# source.net
KiCad netlist of a schematic drawn in EasyEDA Pro
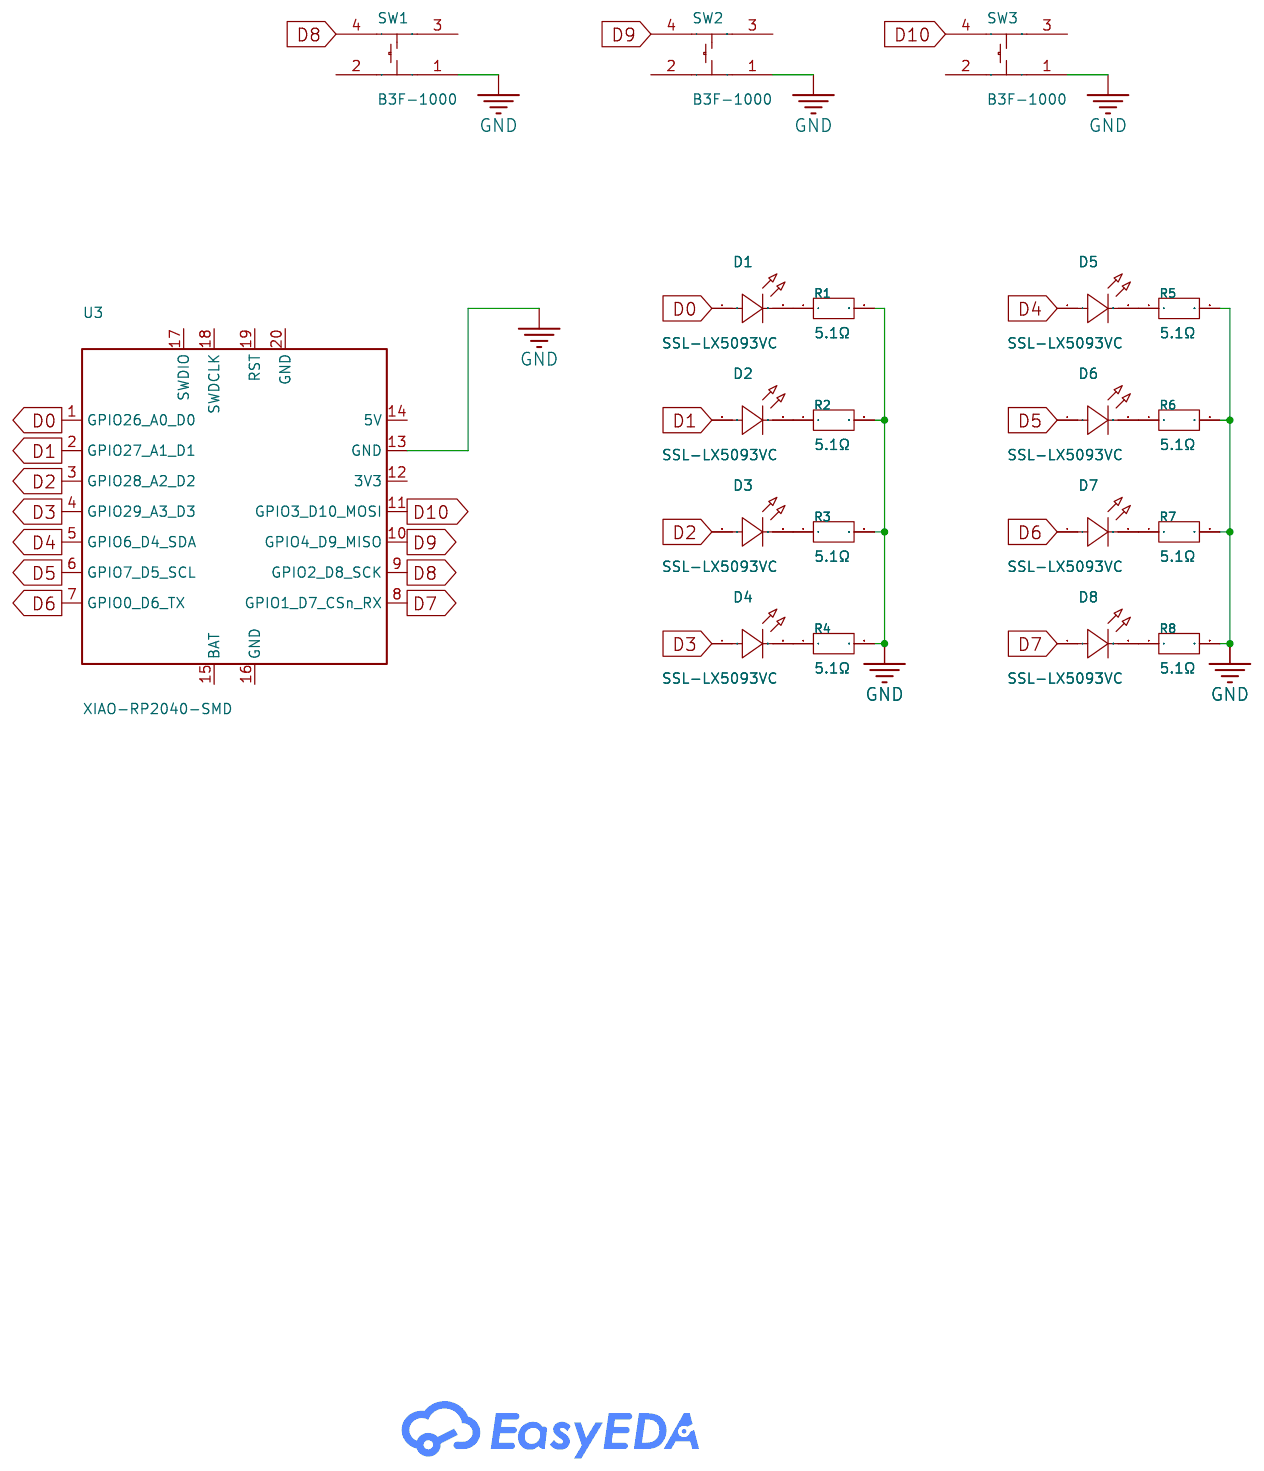
[diagram p0: schematic sheet]

(export (version "E")
  (design (tool "Eeschema 10.0.6"))
  (components
    (comp (ref "D1")
      (value "SSL-LX5093VC")
      (footprint "easyedapro:LED-TH_BD5.0-P2.54-FD")
      (fields (field (name "Manufacturer") "Kingbright"))
      (libsource (lib "easyedapro") (part "WP7113SGC"))
    )
    (comp (ref "D2")
      (value "SSL-LX5093VC")
      (footprint "easyedapro:LED-TH_BD5.0-P2.54-FD")
      (fields (field (name "Manufacturer") "Kingbright"))
      (libsource (lib "easyedapro") (part "WP7113SGC"))
    )
    (comp (ref "D3")
      (value "SSL-LX5093VC")
      (footprint "easyedapro:LED-TH_BD5.0-P2.54-FD")
      (fields (field (name "Manufacturer") "Kingbright"))
      (libsource (lib "easyedapro") (part "WP7113SGC"))
    )
    (comp (ref "D4")
      (value "SSL-LX5093VC")
      (footprint "easyedapro:LED-TH_BD5.0-P2.54-FD")
      (fields (field (name "Manufacturer") "Kingbright"))
      (libsource (lib "easyedapro") (part "WP7113SGC"))
    )
    (comp (ref "D5")
      (value "SSL-LX5093VC")
      (footprint "easyedapro:LED-TH_BD5.0-P2.54-FD")
      (fields (field (name "Manufacturer") "Kingbright"))
      (libsource (lib "easyedapro") (part "WP7113SGC"))
    )
    (comp (ref "D6")
      (value "SSL-LX5093VC")
      (footprint "easyedapro:LED-TH_BD5.0-P2.54-FD")
      (fields (field (name "Manufacturer") "Kingbright"))
      (libsource (lib "easyedapro") (part "WP7113SGC"))
    )
    (comp (ref "D7")
      (value "SSL-LX5093VC")
      (footprint "easyedapro:LED-TH_BD5.0-P2.54-FD")
      (fields (field (name "Manufacturer") "Kingbright"))
      (libsource (lib "easyedapro") (part "WP7113SGC"))
    )
    (comp (ref "D8")
      (value "SSL-LX5093VC")
      (footprint "easyedapro:LED-TH_BD5.0-P2.54-FD")
      (fields (field (name "Manufacturer") "Kingbright"))
      (libsource (lib "easyedapro") (part "WP7113SGC"))
    )
    (comp (ref "R1")
      (value "5.1Ω")
      (footprint "easyedapro:RES-TH_BD2.4-L6.3-P10.30-D0.6")
      (fields (field (name "Manufacturer Part") "CFR-25JB-52-5R1") (field (name "Manufacturer") "YAGEO(国巨)"))
      (libsource (lib "easyedapro") (part "CFR-25JB-52-5R1"))
    )
    (comp (ref "R2")
      (value "5.1Ω")
      (footprint "easyedapro:RES-TH_BD2.4-L6.3-P10.30-D0.6")
      (fields (field (name "Manufacturer Part") "CFR-25JB-52-5R1") (field (name "Manufacturer") "YAGEO(国巨)"))
      (libsource (lib "easyedapro") (part "CFR-25JB-52-5R1"))
    )
    (comp (ref "R3")
      (value "5.1Ω")
      (footprint "easyedapro:RES-TH_BD2.4-L6.3-P10.30-D0.6")
      (fields (field (name "Manufacturer Part") "CFR-25JB-52-5R1") (field (name "Manufacturer") "YAGEO(国巨)"))
      (libsource (lib "easyedapro") (part "CFR-25JB-52-5R1"))
    )
    (comp (ref "R4")
      (value "5.1Ω")
      (footprint "easyedapro:RES-TH_BD2.4-L6.3-P10.30-D0.6")
      (fields (field (name "Manufacturer Part") "CFR-25JB-52-5R1") (field (name "Manufacturer") "YAGEO(国巨)"))
      (libsource (lib "easyedapro") (part "CFR-25JB-52-5R1"))
    )
    (comp (ref "R5")
      (value "5.1Ω")
      (footprint "easyedapro:RES-TH_BD2.4-L6.3-P10.30-D0.6")
      (fields (field (name "Manufacturer Part") "CFR-25JB-52-5R1") (field (name "Manufacturer") "YAGEO(国巨)"))
      (libsource (lib "easyedapro") (part "CFR-25JB-52-5R1"))
    )
    (comp (ref "R6")
      (value "5.1Ω")
      (footprint "easyedapro:RES-TH_BD2.4-L6.3-P10.30-D0.6")
      (fields (field (name "Manufacturer Part") "CFR-25JB-52-5R1") (field (name "Manufacturer") "YAGEO(国巨)"))
      (libsource (lib "easyedapro") (part "CFR-25JB-52-5R1"))
    )
    (comp (ref "R7")
      (value "5.1Ω")
      (footprint "easyedapro:RES-TH_BD2.4-L6.3-P10.30-D0.6")
      (fields (field (name "Manufacturer Part") "CFR-25JB-52-5R1") (field (name "Manufacturer") "YAGEO(国巨)"))
      (libsource (lib "easyedapro") (part "CFR-25JB-52-5R1"))
    )
    (comp (ref "R8")
      (value "5.1Ω")
      (footprint "easyedapro:RES-TH_BD2.4-L6.3-P10.30-D0.6")
      (fields (field (name "Manufacturer Part") "CFR-25JB-52-5R1") (field (name "Manufacturer") "YAGEO(国巨)"))
      (libsource (lib "easyedapro") (part "CFR-25JB-52-5R1"))
    )
    (comp (ref "SW1")
      (value "B3F-1000")
      (footprint "easyedapro:KEY-TH_4P-L6.2-W6.2-P4.50-LS6.5")
      (fields (field (name "Manufacturer") "OMRON(欧姆龙)"))
      (libsource (lib "easyedapro") (part "B3F-1000"))
    )
    (comp (ref "SW2")
      (value "B3F-1000")
      (footprint "easyedapro:KEY-TH_4P-L6.2-W6.2-P4.50-LS6.5")
      (fields (field (name "Manufacturer") "OMRON(欧姆龙)"))
      (libsource (lib "easyedapro") (part "B3F-1000"))
    )
    (comp (ref "SW3")
      (value "B3F-1000")
      (footprint "easyedapro:KEY-TH_4P-L6.2-W6.2-P4.50-LS6.5")
      (fields (field (name "Manufacturer") "OMRON(欧姆龙)"))
      (libsource (lib "easyedapro") (part "B3F-1000"))
    )
    (comp (ref "U3")
      (value "XIAO-RP2040-SMD")
      (footprint "easyedapro:XIAO-RP2040-DIP")
      (libsource (lib "easyedapro") (part "XIAO-RP2040-SMD"))
    )
  )
  (nets
    (net (code "1") (name "D0") (class "Default")
      (node (ref "D1") (pin "1") (pinfunction "1_1") (pintype "unspecified"))
      (node (ref "U3") (pin "1") (pinfunction "GPIO26_A0_D0_1") (pintype "unspecified"))
    )
    (net (code "2") (name "D1") (class "Default")
      (node (ref "D2") (pin "1") (pinfunction "1_1") (pintype "unspecified"))
      (node (ref "U3") (pin "2") (pinfunction "GPIO27_A1_D1_2") (pintype "unspecified"))
    )
    (net (code "3") (name "D2") (class "Default")
      (node (ref "D3") (pin "1") (pinfunction "1_1") (pintype "unspecified"))
      (node (ref "U3") (pin "3") (pinfunction "GPIO28_A2_D2_3") (pintype "unspecified"))
    )
    (net (code "4") (name "D3") (class "Default")
      (node (ref "D4") (pin "1") (pinfunction "1_1") (pintype "unspecified"))
      (node (ref "U3") (pin "4") (pinfunction "GPIO29_A3_D3_4") (pintype "unspecified"))
    )
    (net (code "5") (name "D4") (class "Default")
      (node (ref "D5") (pin "1") (pinfunction "1_1") (pintype "unspecified"))
      (node (ref "U3") (pin "5") (pinfunction "GPIO6_D4_SDA_5") (pintype "unspecified"))
    )
    (net (code "6") (name "D5") (class "Default")
      (node (ref "D6") (pin "1") (pinfunction "1_1") (pintype "unspecified"))
      (node (ref "U3") (pin "6") (pinfunction "GPIO7_D5_SCL_6") (pintype "unspecified"))
    )
    (net (code "7") (name "D6") (class "Default")
      (node (ref "D7") (pin "1") (pinfunction "1_1") (pintype "unspecified"))
      (node (ref "U3") (pin "7") (pinfunction "GPIO0_D6_TX_7") (pintype "unspecified"))
    )
    (net (code "8") (name "D7") (class "Default")
      (node (ref "D8") (pin "1") (pinfunction "1_1") (pintype "unspecified"))
      (node (ref "U3") (pin "8") (pinfunction "GPIO1_D7_CSn_RX_8") (pintype "unspecified"))
    )
    (net (code "9") (name "D8") (class "Default")
      (node (ref "SW1") (pin "4") (pinfunction "4_4") (pintype "unspecified"))
      (node (ref "U3") (pin "9") (pinfunction "GPIO2_D8_SCK_9") (pintype "unspecified"))
    )
    (net (code "10") (name "D9") (class "Default")
      (node (ref "SW2") (pin "4") (pinfunction "4_4") (pintype "unspecified"))
      (node (ref "U3") (pin "10") (pinfunction "GPIO4_D9_MISO_10") (pintype "unspecified"))
    )
    (net (code "11") (name "D10") (class "Default")
      (node (ref "SW3") (pin "4") (pinfunction "4_4") (pintype "unspecified"))
      (node (ref "U3") (pin "11") (pinfunction "GPIO3_D10_MOSI_11") (pintype "unspecified"))
    )
    (net (code "12") (name "GND") (class "Default")
      (node (ref "R1") (pin "2") (pinfunction "2_2") (pintype "input"))
      (node (ref "R2") (pin "2") (pinfunction "2_2") (pintype "input"))
      (node (ref "R3") (pin "2") (pinfunction "2_2") (pintype "input"))
      (node (ref "R4") (pin "2") (pinfunction "2_2") (pintype "input"))
      (node (ref "R5") (pin "2") (pinfunction "2_2") (pintype "input"))
      (node (ref "R6") (pin "2") (pinfunction "2_2") (pintype "input"))
      (node (ref "R7") (pin "2") (pinfunction "2_2") (pintype "input"))
      (node (ref "R8") (pin "2") (pinfunction "2_2") (pintype "input"))
      (node (ref "SW1") (pin "1") (pinfunction "1_1") (pintype "unspecified"))
      (node (ref "SW2") (pin "1") (pinfunction "1_1") (pintype "unspecified"))
      (node (ref "SW3") (pin "1") (pinfunction "1_1") (pintype "unspecified"))
      (node (ref "U3") (pin "13") (pinfunction "GND_13") (pintype "unspecified"))
    )
    (net (code "13") (name "Net-(D1-Pad2)") (class "Default")
      (node (ref "D1") (pin "2") (pinfunction "2_2") (pintype "unspecified"))
      (node (ref "R1") (pin "1") (pinfunction "1_1") (pintype "input"))
    )
    (net (code "14") (name "Net-(D2-Pad2)") (class "Default")
      (node (ref "D2") (pin "2") (pinfunction "2_2") (pintype "unspecified"))
      (node (ref "R2") (pin "1") (pinfunction "1_1") (pintype "input"))
    )
    (net (code "15") (name "Net-(D3-Pad2)") (class "Default")
      (node (ref "D3") (pin "2") (pinfunction "2_2") (pintype "unspecified"))
      (node (ref "R3") (pin "1") (pinfunction "1_1") (pintype "input"))
    )
    (net (code "16") (name "Net-(D4-Pad2)") (class "Default")
      (node (ref "D4") (pin "2") (pinfunction "2_2") (pintype "unspecified"))
      (node (ref "R4") (pin "1") (pinfunction "1_1") (pintype "input"))
    )
    (net (code "17") (name "Net-(D5-Pad2)") (class "Default")
      (node (ref "D5") (pin "2") (pinfunction "2_2") (pintype "unspecified"))
      (node (ref "R5") (pin "1") (pinfunction "1_1") (pintype "input"))
    )
    (net (code "18") (name "Net-(D6-Pad2)") (class "Default")
      (node (ref "D6") (pin "2") (pinfunction "2_2") (pintype "unspecified"))
      (node (ref "R6") (pin "1") (pinfunction "1_1") (pintype "input"))
    )
    (net (code "19") (name "Net-(D7-Pad2)") (class "Default")
      (node (ref "D7") (pin "2") (pinfunction "2_2") (pintype "unspecified"))
      (node (ref "R7") (pin "1") (pinfunction "1_1") (pintype "input"))
    )
    (net (code "20") (name "Net-(D8-Pad2)") (class "Default")
      (node (ref "D8") (pin "2") (pinfunction "2_2") (pintype "unspecified"))
      (node (ref "R8") (pin "1") (pinfunction "1_1") (pintype "input"))
    )
    (net (code "21") (name "unconnected-(SW1-Pad2)") (class "Default")
      (node (ref "SW1") (pin "2") (pinfunction "2_2") (pintype "unspecified"))
    )
    (net (code "22") (name "unconnected-(SW1-Pad3)") (class "Default")
      (node (ref "SW1") (pin "3") (pinfunction "3_3") (pintype "unspecified"))
    )
    (net (code "23") (name "unconnected-(SW2-Pad2)") (class "Default")
      (node (ref "SW2") (pin "2") (pinfunction "2_2") (pintype "unspecified"))
    )
    (net (code "24") (name "unconnected-(SW2-Pad3)") (class "Default")
      (node (ref "SW2") (pin "3") (pinfunction "3_3") (pintype "unspecified"))
    )
    (net (code "25") (name "unconnected-(SW3-Pad2)") (class "Default")
      (node (ref "SW3") (pin "2") (pinfunction "2_2") (pintype "unspecified"))
    )
    (net (code "26") (name "unconnected-(SW3-Pad3)") (class "Default")
      (node (ref "SW3") (pin "3") (pinfunction "3_3") (pintype "unspecified"))
    )
    (net (code "27") (name "unconnected-(U3-3V3-Pad12)") (class "Default")
      (node (ref "U3") (pin "12") (pinfunction "3V3_12") (pintype "unspecified"))
    )
    (net (code "28") (name "unconnected-(U3-5V-Pad14)") (class "Default")
      (node (ref "U3") (pin "14") (pinfunction "5V_14") (pintype "unspecified"))
    )
    (net (code "29") (name "unconnected-(U3-BAT-Pad15)") (class "Default")
      (node (ref "U3") (pin "15") (pinfunction "BAT_15") (pintype "unspecified"))
    )
    (net (code "30") (name "unconnected-(U3-GND-Pad16)") (class "Default")
      (node (ref "U3") (pin "16") (pinfunction "GND_16") (pintype "unspecified"))
    )
    (net (code "31") (name "unconnected-(U3-GND-Pad20)") (class "Default")
      (node (ref "U3") (pin "20") (pinfunction "GND_20") (pintype "unspecified"))
    )
    (net (code "32") (name "unconnected-(U3-RST-Pad19)") (class "Default")
      (node (ref "U3") (pin "19") (pinfunction "RST_19") (pintype "unspecified"))
    )
    (net (code "33") (name "unconnected-(U3-SWDCLK-Pad18)") (class "Default")
      (node (ref "U3") (pin "18") (pinfunction "SWDCLK_18") (pintype "unspecified"))
    )
    (net (code "34") (name "unconnected-(U3-SWDIO-Pad17)") (class "Default")
      (node (ref "U3") (pin "17") (pinfunction "SWDIO_17") (pintype "unspecified"))
    )
  )
)
